# nbiot_gps.net
KiCad netlist of a schematic drawn in Altium Designer
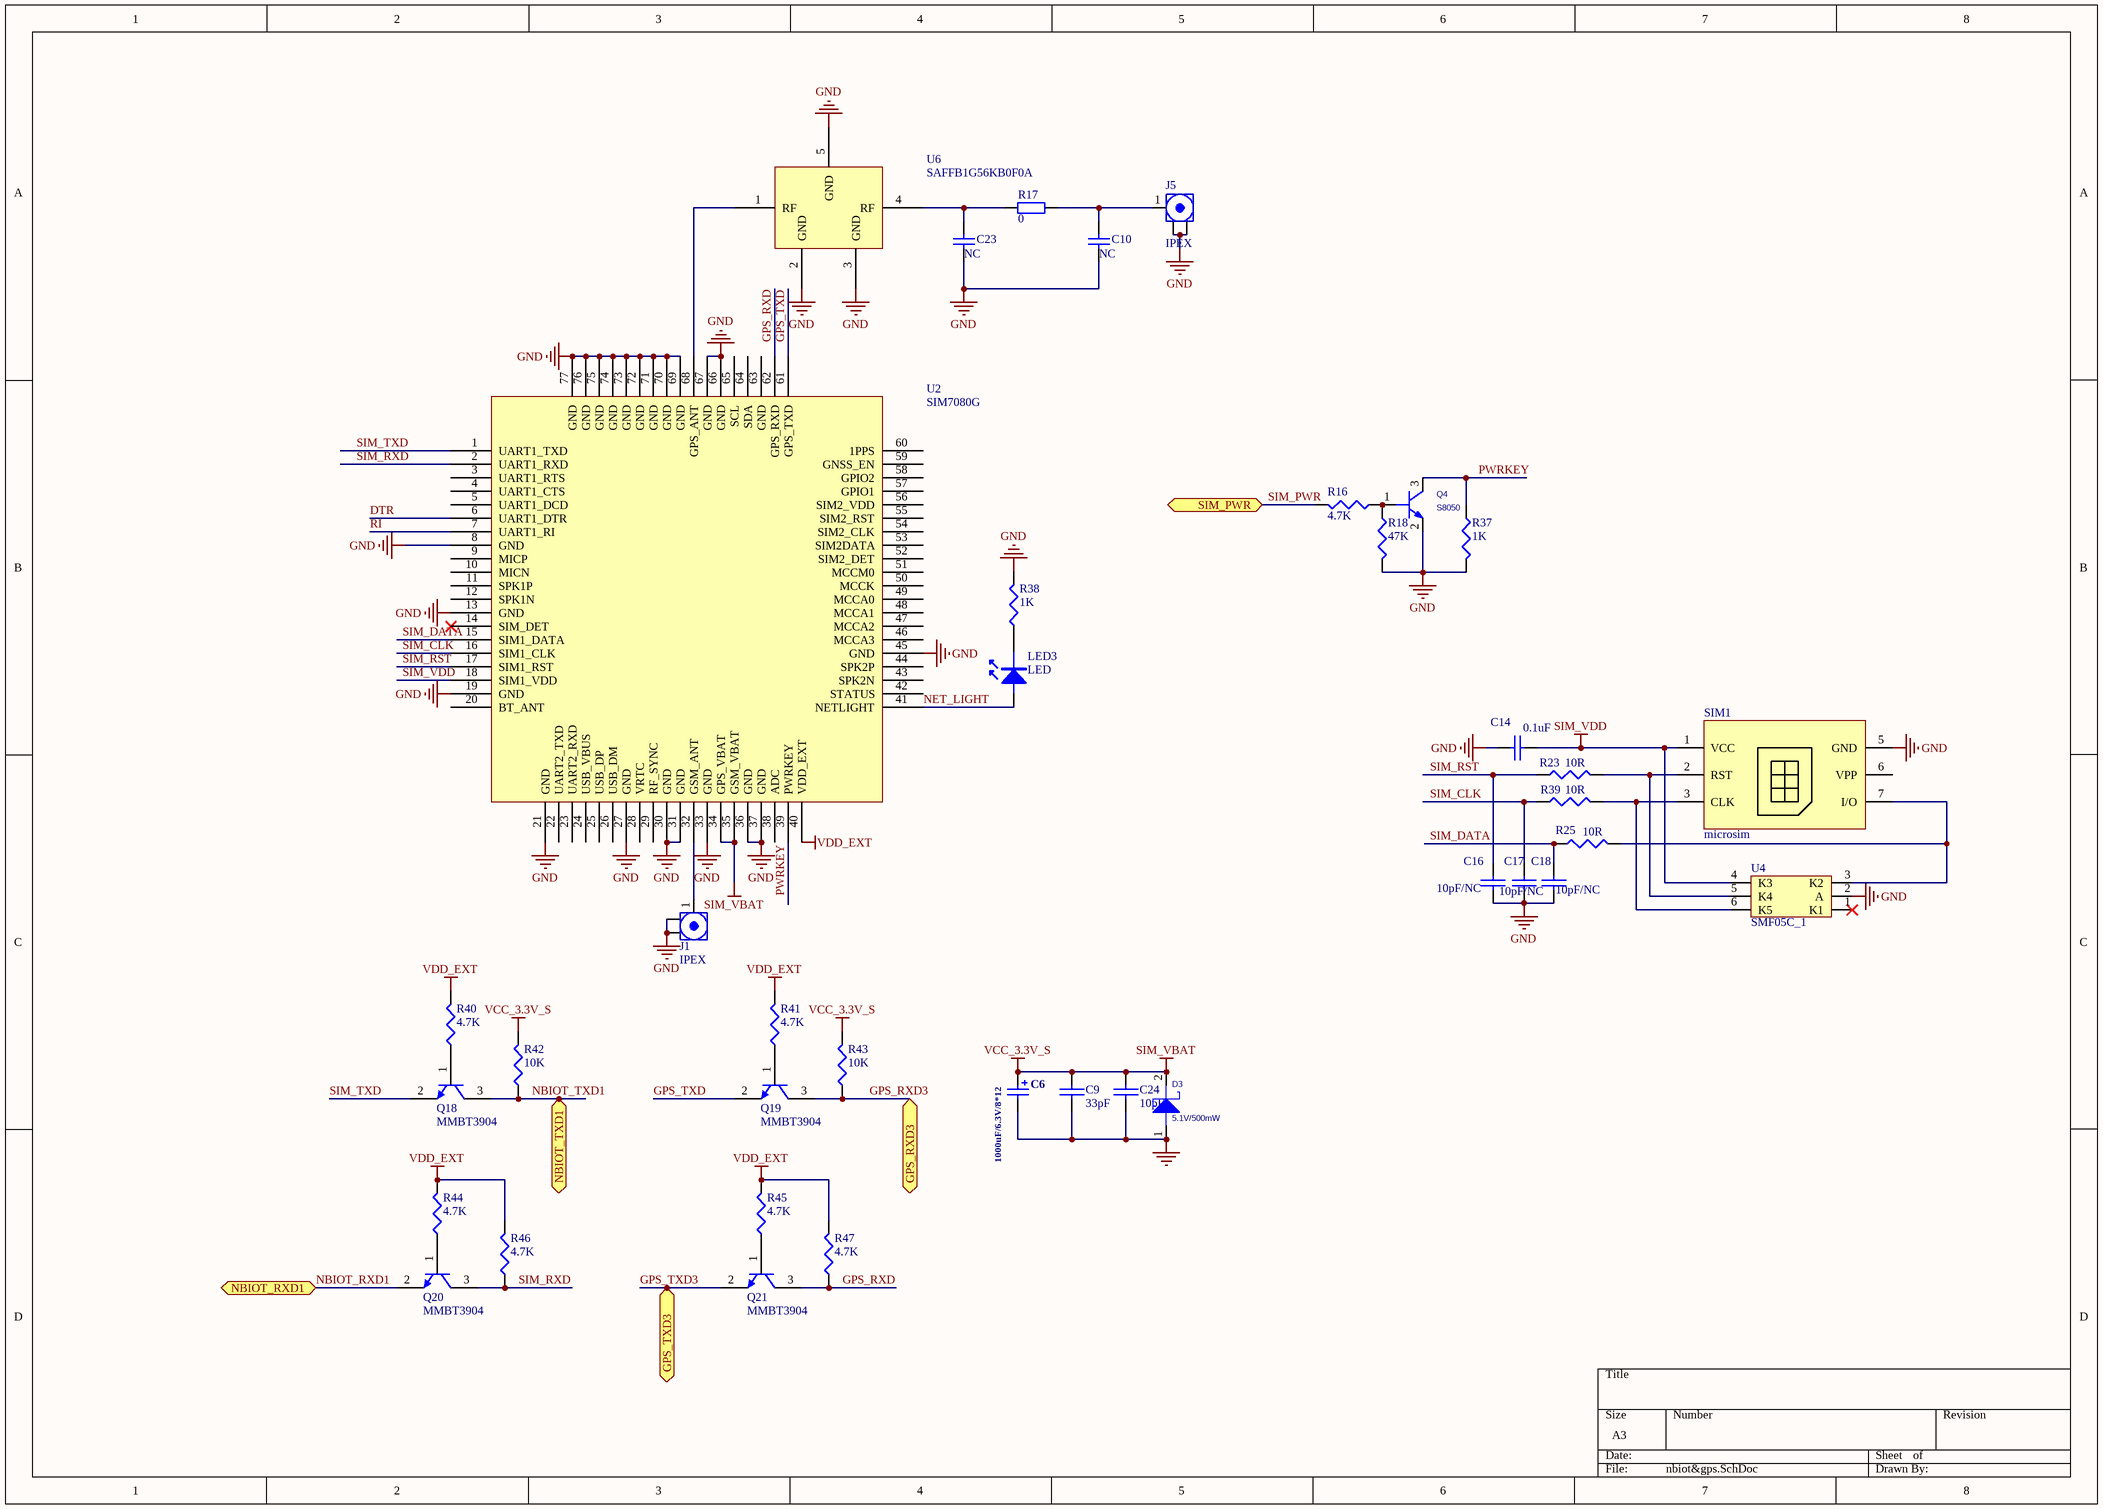
[diagram p0: nbiot&gps.SchDoc]

(export (version "E")
  (design (tool "Eeschema 10.0.6"))
  (components
    (comp (ref "C6")
      (value "1000uF/6.3V/8*12")
      (footprint "8*12")
      (description "Polarized Capacitor (Surface Mount)")
      (libsource (lib "KT_iBeacon") (part "Cap Pol3"))
    )
    (comp (ref "C9")
      (value "33pF")
      (footprint "0603C")
      (description "Capacitor")
      (libsource (lib "ZWLIntegrated_Library") (part "CAP"))
    )
    (comp (ref "C10")
      (value "NC")
      (footprint "0603C")
      (description "Capacitor")
      (fields (field (name "PUBLISHER") "Altium Limited"))
      (libsource (lib "Miscellaneous Devices") (part "Cap"))
    )
    (comp (ref "C14")
      (value "0.1uF")
      (footprint "0603C")
      (description "Capacitor")
      (libsource (lib "ZWLIntegrated_Library") (part "CAP"))
    )
    (comp (ref "C16")
      (value "10pF/NC")
      (footprint "0603C")
      (description "Capacitor")
      (libsource (lib "ZWLIntegrated_Library") (part "CAP"))
    )
    (comp (ref "C17")
      (value "10pF/NC")
      (footprint "0603C")
      (description "Capacitor")
      (libsource (lib "ZWLIntegrated_Library") (part "CAP"))
    )
    (comp (ref "C18")
      (value "10pF/NC")
      (footprint "0603C")
      (description "Capacitor")
      (libsource (lib "ZWLIntegrated_Library") (part "CAP"))
    )
    (comp (ref "C23")
      (value "NC")
      (footprint "0603C")
      (description "Capacitor")
      (fields (field (name "PUBLISHER") "Altium Limited"))
      (libsource (lib "Miscellaneous Devices") (part "Cap"))
    )
    (comp (ref "C24")
      (value "10pF")
      (footprint "0603C")
      (description "Capacitor")
      (libsource (lib "ZWLIntegrated_Library") (part "CAP"))
    )
    (comp (ref "D3")
      (value "5.1V/500mW")
      (footprint "LL-34(D1206)")
      (fields (field (name "Comment") "DIODE_SCHOTTKY_0"))
      (libsource (lib "KT_iBeacon") (part "DIODE_SCHOTTKY_0"))
    )
    (comp (ref "J1") (value "IPEX") (footprint "RF-UFL") (libsource (lib "我的元件库") (part "ANT")))
    (comp (ref "J5") (value "IPEX") (footprint "RF-UFL") (libsource (lib "我的元件库") (part "ANT")))
    (comp (ref "LED3") (value "LED") (footprint "0603LED") (libsource (lib "我的元件库") (part "LED")))
    (comp (ref "Q4") (value "S8050") (footprint "SOT23") (libsource (lib "*") (part "2N1069_1")))
    (comp (ref "Q18") (value "MMBT3904") (footprint "SOT23-3") (libsource (lib "Schlib1") (part "NPN")))
    (comp (ref "Q19") (value "MMBT3904") (footprint "SOT23-3") (libsource (lib "Schlib1") (part "NPN")))
    (comp (ref "Q20") (value "MMBT3904") (footprint "SOT23-3") (libsource (lib "Schlib1") (part "NPN")))
    (comp (ref "Q21") (value "MMBT3904") (footprint "SOT23-3") (libsource (lib "Schlib1") (part "NPN")))
    (comp (ref "R16")
      (value "4.7K")
      (footprint "0603R")
      (libsource (lib "ZWLIntegrated_Library") (part "RES1"))
    )
    (comp (ref "R17")
      (value "0")
      (footprint "0603R")
      (description "Resistor")
      (fields (field (name "PUBLISHER") "Altium Limited"))
      (libsource (lib "Miscellaneous Devices") (part "Res2"))
    )
    (comp (ref "R18")
      (value "47K")
      (footprint "0603R")
      (libsource (lib "ZWLIntegrated_Library") (part "RES1"))
    )
    (comp (ref "R23")
      (value "10R")
      (footprint "0603R")
      (libsource (lib "ZWLIntegrated_Library") (part "RES1"))
    )
    (comp (ref "R25")
      (value "10R")
      (footprint "0603R")
      (libsource (lib "ZWLIntegrated_Library") (part "RES1"))
    )
    (comp (ref "R37")
      (value "1K")
      (footprint "0603R")
      (libsource (lib "ZWLIntegrated_Library") (part "RES1"))
    )
    (comp (ref "R38")
      (value "1K")
      (footprint "0603R")
      (libsource (lib "ZWLIntegrated_Library") (part "RES1"))
    )
    (comp (ref "R39")
      (value "10R")
      (footprint "0603R")
      (libsource (lib "ZWLIntegrated_Library") (part "RES1"))
    )
    (comp (ref "R40")
      (value "4.7K")
      (footprint "0603R")
      (libsource (lib "ZWLIntegrated_Library") (part "RES1"))
    )
    (comp (ref "R41")
      (value "4.7K")
      (footprint "0603R")
      (libsource (lib "ZWLIntegrated_Library") (part "RES1"))
    )
    (comp (ref "R42")
      (value "10K")
      (footprint "0603R")
      (libsource (lib "ZWLIntegrated_Library") (part "RES1"))
    )
    (comp (ref "R43")
      (value "10K")
      (footprint "0603R")
      (libsource (lib "ZWLIntegrated_Library") (part "RES1"))
    )
    (comp (ref "R44")
      (value "4.7K")
      (footprint "0603R")
      (libsource (lib "ZWLIntegrated_Library") (part "RES1"))
    )
    (comp (ref "R45")
      (value "4.7K")
      (footprint "0603R")
      (libsource (lib "ZWLIntegrated_Library") (part "RES1"))
    )
    (comp (ref "R46")
      (value "4.7K")
      (footprint "0603R")
      (libsource (lib "ZWLIntegrated_Library") (part "RES1"))
    )
    (comp (ref "R47")
      (value "4.7K")
      (footprint "0603R")
      (libsource (lib "ZWLIntegrated_Library") (part "RES1"))
    )
    (comp (ref "SIM1")
      (value "microsim")
      (footprint "Nano SIM")
      (libsource (lib "SIM800C 原理图库") (part "microsim"))
    )
    (comp (ref "U2")
      (value "SIM7080G")
      (footprint "SIM868")
      (libsource (lib "stm32") (part "SIM868E/SIM868"))
    )
    (comp (ref "U4")
      (value "SMF05C_1")
      (footprint "SC70-6L")
      (description "TVS")
      (libsource (lib "SIM800C 原理图库") (part "SMF05C_1"))
    )
    (comp (ref "U6")
      (value "SAFFB1G56KB0F0A")
      (footprint "SAFFB1G56KB0F0A")
      (libsource (lib "stm32") (part "SAFFB1G56KBOFA"))
    )
  )
  (nets
    (net (code "1") (name "/DTR") (class "Default")
      (node (ref "U2") (pin "6") (pinfunction "UART1_DTR_6") (pintype "passive"))
    )
    (net (code "2") (name "/GPS_RXD") (class "Default")
      (node (ref "Q21") (pin "3") (pinfunction "C_3") (pintype "passive"))
      (node (ref "R47") (pin "1") (pinfunction "1_1") (pintype "passive"))
      (node (ref "U2") (pin "62") (pinfunction "GPS_RXD_62") (pintype "passive"))
    )
    (net (code "3") (name "/GPS_RXD3") (class "Default")
      (node (ref "Q19") (pin "3") (pinfunction "C_3") (pintype "passive"))
      (node (ref "R43") (pin "1") (pinfunction "1_1") (pintype "passive"))
    )
    (net (code "4") (name "/GPS_TXD") (class "Default")
      (node (ref "Q19") (pin "2") (pinfunction "E_2") (pintype "passive"))
      (node (ref "U2") (pin "61") (pinfunction "GPS_TXD_61") (pintype "passive"))
    )
    (net (code "5") (name "/GPS_TXD3") (class "Default")
      (node (ref "Q21") (pin "2") (pinfunction "E_2") (pintype "passive"))
    )
    (net (code "6") (name "/NBIOT_RXD1") (class "Default")
      (node (ref "Q20") (pin "2") (pinfunction "E_2") (pintype "passive"))
    )
    (net (code "7") (name "/NBIOT_TXD1") (class "Default")
      (node (ref "Q18") (pin "3") (pinfunction "C_3") (pintype "passive"))
      (node (ref "R42") (pin "1") (pinfunction "1_1") (pintype "passive"))
    )
    (net (code "8") (name "/NET_LIGHT") (class "Default")
      (node (ref "LED3") (pin "1") (pinfunction "1_1") (pintype "passive"))
      (node (ref "U2") (pin "41") (pinfunction "NETLIGHT_41") (pintype "passive"))
    )
    (net (code "9") (name "/PWRKEY") (class "Default")
      (node (ref "Q4") (pin "3") (pinfunction "C_3") (pintype "passive"))
      (node (ref "R37") (pin "1") (pinfunction "1_1") (pintype "passive"))
      (node (ref "U2") (pin "39") (pinfunction "PWRKEY_39") (pintype "passive"))
    )
    (net (code "10") (name "/RI") (class "Default")
      (node (ref "U2") (pin "7") (pinfunction "UART1_RI_7") (pintype "passive"))
    )
    (net (code "11") (name "/SIM_CLK") (class "Default")
      (node (ref "C17") (pin "2") (pinfunction "2_2") (pintype "passive"))
      (node (ref "R39") (pin "1") (pinfunction "1_1") (pintype "passive"))
      (node (ref "U2") (pin "16") (pinfunction "SIM1_CLK_16") (pintype "passive"))
    )
    (net (code "12") (name "/SIM_DATA") (class "Default")
      (node (ref "C18") (pin "2") (pinfunction "2_2") (pintype "passive"))
      (node (ref "R25") (pin "1") (pinfunction "1_1") (pintype "passive"))
      (node (ref "U2") (pin "15") (pinfunction "SIM1_DATA_15") (pintype "passive"))
    )
    (net (code "13") (name "/SIM_PWR") (class "Default")
      (node (ref "R16") (pin "2") (pinfunction "2_2") (pintype "passive"))
    )
    (net (code "14") (name "/SIM_RST") (class "Default")
      (node (ref "C16") (pin "2") (pinfunction "2_2") (pintype "passive"))
      (node (ref "R23") (pin "1") (pinfunction "1_1") (pintype "passive"))
      (node (ref "U2") (pin "17") (pinfunction "SIM1_RST_17") (pintype "passive"))
    )
    (net (code "15") (name "/SIM_RXD") (class "Default")
      (node (ref "Q20") (pin "3") (pinfunction "C_3") (pintype "passive"))
      (node (ref "R46") (pin "1") (pinfunction "1_1") (pintype "passive"))
      (node (ref "U2") (pin "2") (pinfunction "UART1_RXD_2") (pintype "passive"))
    )
    (net (code "16") (name "/SIM_TXD") (class "Default")
      (node (ref "Q18") (pin "2") (pinfunction "E_2") (pintype "passive"))
      (node (ref "U2") (pin "1") (pinfunction "UART1_TXD_1") (pintype "passive"))
    )
    (net (code "17") (name "GND") (class "Default")
      (node (ref "C10") (pin "2") (pinfunction "2_2") (pintype "passive"))
      (node (ref "C14") (pin "1") (pinfunction "1_1") (pintype "passive"))
      (node (ref "C16") (pin "1") (pinfunction "1_1") (pintype "passive"))
      (node (ref "C17") (pin "1") (pinfunction "1_1") (pintype "passive"))
      (node (ref "C18") (pin "1") (pinfunction "1_1") (pintype "passive"))
      (node (ref "C23") (pin "2") (pinfunction "2_2") (pintype "passive"))
      (node (ref "C24") (pin "1") (pinfunction "1_1") (pintype "passive"))
      (node (ref "C6") (pin "2") (pinfunction "2_2") (pintype "passive"))
      (node (ref "C9") (pin "1") (pinfunction "1_1") (pintype "passive"))
      (node (ref "D3") (pin "1") (pinfunction "1_1") (pintype "passive"))
      (node (ref "J1") (pin "2") (pinfunction "Y_2") (pintype "passive"))
      (node (ref "J5") (pin "2") (pinfunction "Y_2") (pintype "passive"))
      (node (ref "Q4") (pin "2") (pinfunction "E_2") (pintype "passive"))
      (node (ref "R18") (pin "2") (pinfunction "2_2") (pintype "passive"))
      (node (ref "R37") (pin "2") (pinfunction "2_2") (pintype "passive"))
      (node (ref "R38") (pin "2") (pinfunction "2_2") (pintype "passive"))
      (node (ref "SIM1") (pin "5") (pinfunction "GND_5") (pintype "passive"))
      (node (ref "U2") (pin "13") (pinfunction "GND_13") (pintype "passive"))
      (node (ref "U2") (pin "19") (pinfunction "GND_19") (pintype "passive"))
      (node (ref "U2") (pin "21") (pinfunction "GND_21") (pintype "passive"))
      (node (ref "U2") (pin "27") (pinfunction "GND_27") (pintype "passive"))
      (node (ref "U2") (pin "30") (pinfunction "GND_30") (pintype "passive"))
      (node (ref "U2") (pin "31") (pinfunction "GND_31") (pintype "passive"))
      (node (ref "U2") (pin "33") (pinfunction "GND_33") (pintype "passive"))
      (node (ref "U2") (pin "36") (pinfunction "GND_36") (pintype "passive"))
      (node (ref "U2") (pin "37") (pinfunction "GND_37") (pintype "passive"))
      (node (ref "U2") (pin "45") (pinfunction "GND_45") (pintype "passive"))
      (node (ref "U2") (pin "66") (pinfunction "GND_66") (pintype "passive"))
      (node (ref "U2") (pin "67") (pinfunction "GND_67") (pintype "passive"))
      (node (ref "U2") (pin "69") (pinfunction "GND_69") (pintype "passive"))
      (node (ref "U2") (pin "70") (pinfunction "GND_70") (pintype "passive"))
      (node (ref "U2") (pin "71") (pinfunction "GND_71") (pintype "passive"))
      (node (ref "U2") (pin "72") (pinfunction "GND_72") (pintype "passive"))
      (node (ref "U2") (pin "73") (pinfunction "GND_73") (pintype "passive"))
      (node (ref "U2") (pin "74") (pinfunction "GND_74") (pintype "passive"))
      (node (ref "U2") (pin "75") (pinfunction "GND_75") (pintype "passive"))
      (node (ref "U2") (pin "76") (pinfunction "GND_76") (pintype "passive"))
      (node (ref "U2") (pin "77") (pinfunction "GND_77") (pintype "passive"))
      (node (ref "U2") (pin "8") (pinfunction "GND_8") (pintype "passive"))
      (node (ref "U4") (pin "2") (pinfunction "A_2") (pintype "passive"))
      (node (ref "U6") (pin "2") (pinfunction "GND_2") (pintype "passive"))
      (node (ref "U6") (pin "3") (pinfunction "GND_3") (pintype "passive"))
      (node (ref "U6") (pin "5") (pinfunction "GND_5") (pintype "passive"))
    )
    (net (code "18") (name "Net-(C23-Pad1)") (class "Default")
      (node (ref "C23") (pin "1") (pinfunction "1_1") (pintype "passive"))
      (node (ref "R17") (pin "1") (pinfunction "1_1") (pintype "passive"))
      (node (ref "U6") (pin "4") (pinfunction "RF_4") (pintype "passive"))
    )
    (net (code "19") (name "Net-(J1-X)") (class "Default")
      (node (ref "J1") (pin "1") (pinfunction "X_1") (pintype "passive"))
      (node (ref "U2") (pin "32") (pinfunction "GSM_ANT_32") (pintype "passive"))
    )
    (net (code "20") (name "Net-(J5-X)") (class "Default")
      (node (ref "C10") (pin "1") (pinfunction "1_1") (pintype "passive"))
      (node (ref "J5") (pin "1") (pinfunction "X_1") (pintype "passive"))
      (node (ref "R17") (pin "2") (pinfunction "2_2") (pintype "passive"))
    )
    (net (code "21") (name "Net-(LED3-Pad2)") (class "Default")
      (node (ref "LED3") (pin "2") (pinfunction "2_2") (pintype "passive"))
      (node (ref "R38") (pin "1") (pinfunction "1_1") (pintype "passive"))
    )
    (net (code "22") (name "Net-(Q4-B)") (class "Default")
      (node (ref "Q4") (pin "1") (pinfunction "B_1") (pintype "passive"))
      (node (ref "R16") (pin "1") (pinfunction "1_1") (pintype "passive"))
      (node (ref "R18") (pin "1") (pinfunction "1_1") (pintype "passive"))
    )
    (net (code "23") (name "Net-(Q18-B)") (class "Default")
      (node (ref "Q18") (pin "1") (pinfunction "B_1") (pintype "passive"))
      (node (ref "R40") (pin "1") (pinfunction "1_1") (pintype "passive"))
    )
    (net (code "24") (name "Net-(Q19-B)") (class "Default")
      (node (ref "Q19") (pin "1") (pinfunction "B_1") (pintype "passive"))
      (node (ref "R41") (pin "1") (pinfunction "1_1") (pintype "passive"))
    )
    (net (code "25") (name "Net-(Q20-B)") (class "Default")
      (node (ref "Q20") (pin "1") (pinfunction "B_1") (pintype "passive"))
      (node (ref "R44") (pin "1") (pinfunction "1_1") (pintype "passive"))
    )
    (net (code "26") (name "Net-(Q21-B)") (class "Default")
      (node (ref "Q21") (pin "1") (pinfunction "B_1") (pintype "passive"))
      (node (ref "R45") (pin "1") (pinfunction "1_1") (pintype "passive"))
    )
    (net (code "27") (name "Net-(SIM1-CLK)") (class "Default")
      (node (ref "R39") (pin "2") (pinfunction "2_2") (pintype "passive"))
      (node (ref "SIM1") (pin "3") (pinfunction "CLK_3") (pintype "passive"))
      (node (ref "U4") (pin "6") (pinfunction "K5_6") (pintype "passive"))
    )
    (net (code "28") (name "Net-(SIM1-I{slash}O)") (class "Default")
      (node (ref "R25") (pin "2") (pinfunction "2_2") (pintype "passive"))
      (node (ref "SIM1") (pin "7") (pinfunction "I/O_7") (pintype "passive"))
      (node (ref "U4") (pin "3") (pinfunction "K2_3") (pintype "passive"))
    )
    (net (code "29") (name "Net-(SIM1-RST)") (class "Default")
      (node (ref "R23") (pin "2") (pinfunction "2_2") (pintype "passive"))
      (node (ref "SIM1") (pin "2") (pinfunction "RST_2") (pintype "passive"))
      (node (ref "U4") (pin "5") (pinfunction "K4_5") (pintype "passive"))
    )
    (net (code "30") (name "Net-(U2-GPS_ANT)") (class "Default")
      (node (ref "U2") (pin "68") (pinfunction "GPS_ANT_68") (pintype "passive"))
      (node (ref "U6") (pin "1") (pinfunction "RF_1") (pintype "passive"))
    )
    (net (code "31") (name "SIM_VBAT") (class "Default")
      (node (ref "C24") (pin "2") (pinfunction "2_2") (pintype "passive"))
      (node (ref "C6") (pin "1") (pinfunction "1_1") (pintype "passive"))
      (node (ref "C9") (pin "2") (pinfunction "2_2") (pintype "passive"))
      (node (ref "D3") (pin "2") (pinfunction "2_2") (pintype "passive"))
      (node (ref "R42") (pin "2") (pinfunction "2_2") (pintype "passive"))
      (node (ref "R43") (pin "2") (pinfunction "2_2") (pintype "passive"))
      (node (ref "U2") (pin "34") (pinfunction "GPS_VBAT_34") (pintype "passive"))
      (node (ref "U2") (pin "35") (pinfunction "GSM_VBAT_35") (pintype "passive"))
    )
    (net (code "32") (name "SIM_VDD") (class "Default")
      (node (ref "C14") (pin "2") (pinfunction "2_2") (pintype "passive"))
      (node (ref "SIM1") (pin "1") (pinfunction "VCC_1") (pintype "passive"))
      (node (ref "U2") (pin "18") (pinfunction "SIM1_VDD_18") (pintype "passive"))
      (node (ref "U4") (pin "4") (pinfunction "K3_4") (pintype "passive"))
    )
    (net (code "33") (name "VDD_EXT") (class "Default")
      (node (ref "R40") (pin "2") (pinfunction "2_2") (pintype "passive"))
      (node (ref "R41") (pin "2") (pinfunction "2_2") (pintype "passive"))
      (node (ref "R44") (pin "2") (pinfunction "2_2") (pintype "passive"))
      (node (ref "R45") (pin "2") (pinfunction "2_2") (pintype "passive"))
      (node (ref "R46") (pin "2") (pinfunction "2_2") (pintype "passive"))
      (node (ref "R47") (pin "2") (pinfunction "2_2") (pintype "passive"))
      (node (ref "U2") (pin "40") (pinfunction "VDD_EXT_40") (pintype "passive"))
    )
    (net (code "34") (name "unconnected-(SIM1-VPP-Pad6)") (class "Default")
      (node (ref "SIM1") (pin "6") (pinfunction "VPP_6") (pintype "passive"))
    )
    (net (code "35") (name "unconnected-(U2-1PPS-Pad60)") (class "Default")
      (node (ref "U2") (pin "60") (pinfunction "1PPS_60") (pintype "passive"))
    )
    (net (code "36") (name "unconnected-(U2-ADC-Pad38)") (class "Default")
      (node (ref "U2") (pin "38") (pinfunction "ADC_38") (pintype "passive"))
    )
    (net (code "37") (name "unconnected-(U2-BT_ANT-Pad20)") (class "Default")
      (node (ref "U2") (pin "20") (pinfunction "BT_ANT_20") (pintype "passive"))
    )
    (net (code "38") (name "unconnected-(U2-GND-Pad63)") (class "Default")
      (node (ref "U2") (pin "63") (pinfunction "GND_63") (pintype "passive"))
    )
    (net (code "39") (name "unconnected-(U2-GNSS_EN-Pad59)") (class "Default")
      (node (ref "U2") (pin "59") (pinfunction "GNSS_EN_59") (pintype "passive"))
    )
    (net (code "40") (name "unconnected-(U2-GPIO1-Pad57)") (class "Default")
      (node (ref "U2") (pin "57") (pinfunction "GPIO1_57") (pintype "passive"))
    )
    (net (code "41") (name "unconnected-(U2-GPIO2-Pad58)") (class "Default")
      (node (ref "U2") (pin "58") (pinfunction "GPIO2_58") (pintype "passive"))
    )
    (net (code "42") (name "unconnected-(U2-MCCA0-Pad49)") (class "Default")
      (node (ref "U2") (pin "49") (pinfunction "MCCA0_49") (pintype "passive"))
    )
    (net (code "43") (name "unconnected-(U2-MCCA1-Pad48)") (class "Default")
      (node (ref "U2") (pin "48") (pinfunction "MCCA1_48") (pintype "passive"))
    )
    (net (code "44") (name "unconnected-(U2-MCCA2-Pad47)") (class "Default")
      (node (ref "U2") (pin "47") (pinfunction "MCCA2_47") (pintype "passive"))
    )
    (net (code "45") (name "unconnected-(U2-MCCA3-Pad46)") (class "Default")
      (node (ref "U2") (pin "46") (pinfunction "MCCA3_46") (pintype "passive"))
    )
    (net (code "46") (name "unconnected-(U2-MCCK-Pad50)") (class "Default")
      (node (ref "U2") (pin "50") (pinfunction "MCCK_50") (pintype "passive"))
    )
    (net (code "47") (name "unconnected-(U2-MCCM0-Pad51)") (class "Default")
      (node (ref "U2") (pin "51") (pinfunction "MCCM0_51") (pintype "passive"))
    )
    (net (code "48") (name "unconnected-(U2-MICN-Pad10)") (class "Default")
      (node (ref "U2") (pin "10") (pinfunction "MICN_10") (pintype "passive"))
    )
    (net (code "49") (name "unconnected-(U2-MICP-Pad9)") (class "Default")
      (node (ref "U2") (pin "9") (pinfunction "MICP_9") (pintype "passive"))
    )
    (net (code "50") (name "unconnected-(U2-RF_SYNC-Pad29)") (class "Default")
      (node (ref "U2") (pin "29") (pinfunction "RF_SYNC_29") (pintype "passive"))
    )
    (net (code "51") (name "unconnected-(U2-SCL-Pad65)") (class "Default")
      (node (ref "U2") (pin "65") (pinfunction "SCL_65") (pintype "passive"))
    )
    (net (code "52") (name "unconnected-(U2-SDA-Pad64)") (class "Default")
      (node (ref "U2") (pin "64") (pinfunction "SDA_64") (pintype "passive"))
    )
    (net (code "53") (name "unconnected-(U2-SIM2DATA-Pad53)") (class "Default")
      (node (ref "U2") (pin "53") (pinfunction "SIM2DATA_53") (pintype "passive"))
    )
    (net (code "54") (name "unconnected-(U2-SIM2_CLK-Pad54)") (class "Default")
      (node (ref "U2") (pin "54") (pinfunction "SIM2_CLK_54") (pintype "passive"))
    )
    (net (code "55") (name "unconnected-(U2-SIM2_DET-Pad52)") (class "Default")
      (node (ref "U2") (pin "52") (pinfunction "SIM2_DET_52") (pintype "passive"))
    )
    (net (code "56") (name "unconnected-(U2-SIM2_RST-Pad55)") (class "Default")
      (node (ref "U2") (pin "55") (pinfunction "SIM2_RST_55") (pintype "passive"))
    )
    (net (code "57") (name "unconnected-(U2-SIM2_VDD-Pad56)") (class "Default")
      (node (ref "U2") (pin "56") (pinfunction "SIM2_VDD_56") (pintype "passive"))
    )
    (net (code "58") (name "unconnected-(U2-SIM_DET-Pad14)") (class "Default")
      (node (ref "U2") (pin "14") (pinfunction "SIM_DET_14") (pintype "passive+no_connect"))
    )
    (net (code "59") (name "unconnected-(U2-SPK1N-Pad12)") (class "Default")
      (node (ref "U2") (pin "12") (pinfunction "SPK1N_12") (pintype "passive"))
    )
    (net (code "60") (name "unconnected-(U2-SPK1P-Pad11)") (class "Default")
      (node (ref "U2") (pin "11") (pinfunction "SPK1P_11") (pintype "passive"))
    )
    (net (code "61") (name "unconnected-(U2-SPK2N-Pad43)") (class "Default")
      (node (ref "U2") (pin "43") (pinfunction "SPK2N_43") (pintype "passive"))
    )
    (net (code "62") (name "unconnected-(U2-SPK2P-Pad44)") (class "Default")
      (node (ref "U2") (pin "44") (pinfunction "SPK2P_44") (pintype "passive"))
    )
    (net (code "63") (name "unconnected-(U2-STATUS-Pad42)") (class "Default")
      (node (ref "U2") (pin "42") (pinfunction "STATUS_42") (pintype "passive"))
    )
    (net (code "64") (name "unconnected-(U2-UART1_CTS-Pad4)") (class "Default")
      (node (ref "U2") (pin "4") (pinfunction "UART1_CTS_4") (pintype "passive"))
    )
    (net (code "65") (name "unconnected-(U2-UART1_DCD-Pad5)") (class "Default")
      (node (ref "U2") (pin "5") (pinfunction "UART1_DCD_5") (pintype "passive"))
    )
    (net (code "66") (name "unconnected-(U2-UART1_RTS-Pad3)") (class "Default")
      (node (ref "U2") (pin "3") (pinfunction "UART1_RTS_3") (pintype "passive"))
    )
    (net (code "67") (name "unconnected-(U2-UART2_RXD-Pad23)") (class "Default")
      (node (ref "U2") (pin "23") (pinfunction "UART2_RXD_23") (pintype "passive"))
    )
    (net (code "68") (name "unconnected-(U2-UART2_TXD-Pad22)") (class "Default")
      (node (ref "U2") (pin "22") (pinfunction "UART2_TXD_22") (pintype "passive"))
    )
    (net (code "69") (name "unconnected-(U2-USB_DM-Pad26)") (class "Default")
      (node (ref "U2") (pin "26") (pinfunction "USB_DM_26") (pintype "passive"))
    )
    (net (code "70") (name "unconnected-(U2-USB_DP-Pad25)") (class "Default")
      (node (ref "U2") (pin "25") (pinfunction "USB_DP_25") (pintype "passive"))
    )
    (net (code "71") (name "unconnected-(U2-USB_VBUS-Pad24)") (class "Default")
      (node (ref "U2") (pin "24") (pinfunction "USB_VBUS_24") (pintype "passive"))
    )
    (net (code "72") (name "unconnected-(U2-VRTC-Pad28)") (class "Default")
      (node (ref "U2") (pin "28") (pinfunction "VRTC_28") (pintype "passive"))
    )
    (net (code "73") (name "unconnected-(U4-K1-Pad1)") (class "Default")
      (node (ref "U4") (pin "1") (pinfunction "K1_1") (pintype "passive+no_connect"))
    )
  )
)
